# small.net
KiCad netlist of a schematic drawn in EAGLE
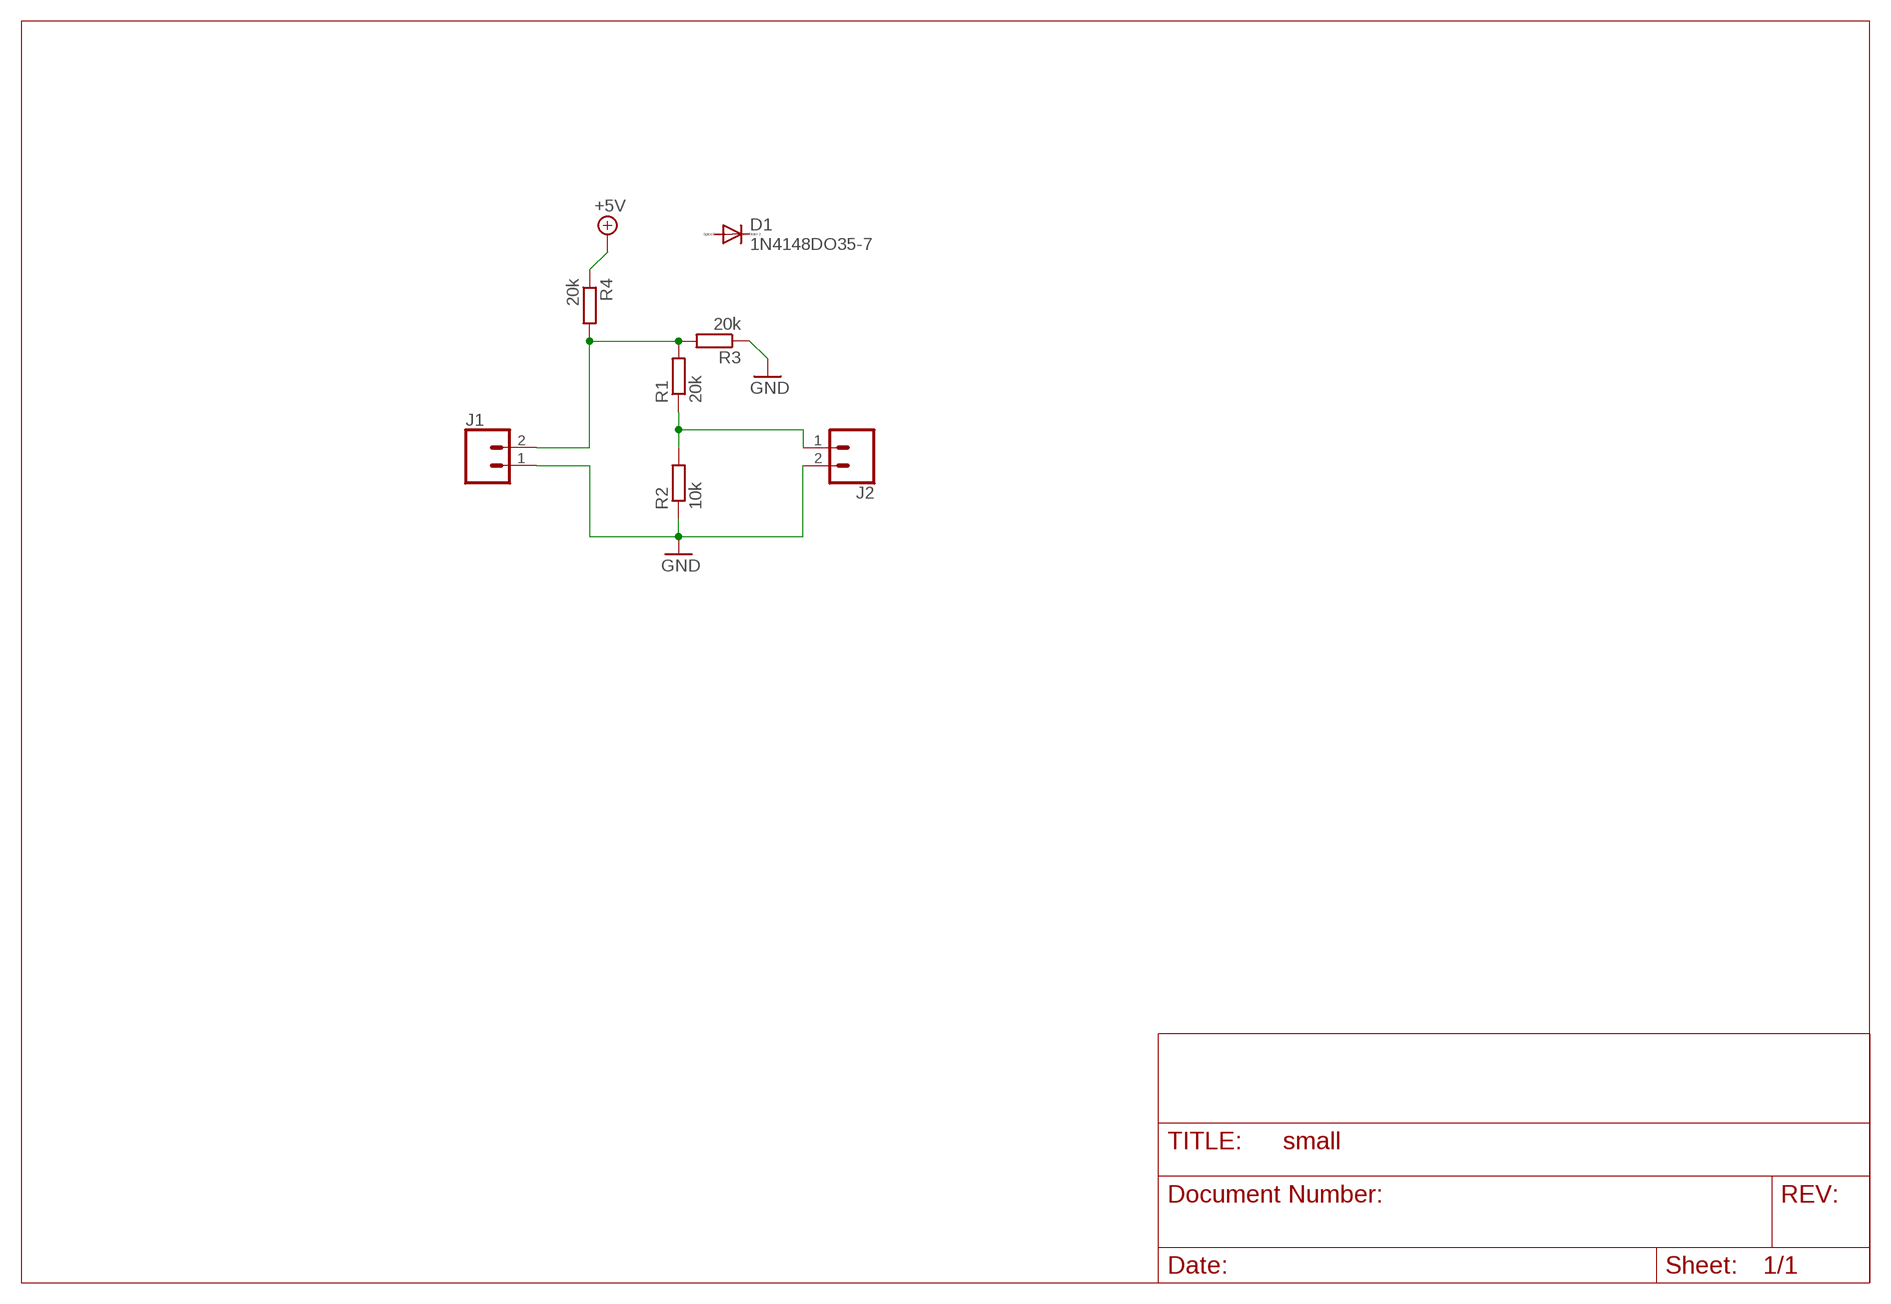
[diagram p0: schematic, sheet 1]

(export (version "E")
  (design (tool "Eeschema 10.0.6"))
  (components
    (comp (ref "D1")
      (value "1N4148DO35-7")
      (footprint "eagle-import:DO35-7")
      (libsource (lib "eagle-import") (part "1N4148DO35-7"))
    )
    (comp (ref "J1")
      (value "CONN_02")
      (footprint "eagle-import:1X02")
      (libsource (lib "eagle-import") (part "CONN_02"))
    )
    (comp (ref "J2")
      (value "CONN_02")
      (footprint "eagle-import:1X02")
      (libsource (lib "eagle-import") (part "CONN_02"))
    )
    (comp (ref "R1")
      (value "20k")
      (footprint "eagle-import:0204_5")
      (libsource (lib "eagle-import") (part "R-EU_0204/5"))
    )
    (comp (ref "R2")
      (value "10k")
      (footprint "eagle-import:0204_5")
      (libsource (lib "eagle-import") (part "R-EU_0204/5"))
    )
    (comp (ref "R3")
      (value "20k")
      (footprint "eagle-import:0204_5")
      (libsource (lib "eagle-import") (part "R-EU_0204/5"))
    )
    (comp (ref "R4")
      (value "20k")
      (footprint "eagle-import:0204_5")
      (libsource (lib "eagle-import") (part "R-EU_0204/5"))
    )
  )
  (nets
    (net (code "1") (name "+5V") (class "Default")
      (node (ref "R4") (pin "1") (pinfunction "1_1") (pintype "passive"))
    )
    (net (code "2") (name "GND") (class "Default")
      (node (ref "J1") (pin "1") (pinfunction "1_1") (pintype "passive"))
      (node (ref "J2") (pin "2") (pinfunction "2_2") (pintype "passive"))
      (node (ref "R2") (pin "1") (pinfunction "1_1") (pintype "passive"))
      (node (ref "R3") (pin "1") (pinfunction "1_1") (pintype "passive"))
    )
    (net (code "3") (name "Net-(J1-Pad2)") (class "Default")
      (node (ref "J1") (pin "2") (pinfunction "2_2") (pintype "passive"))
      (node (ref "R1") (pin "2") (pinfunction "2_2") (pintype "passive"))
      (node (ref "R3") (pin "2") (pinfunction "2_2") (pintype "passive"))
      (node (ref "R4") (pin "2") (pinfunction "2_2") (pintype "passive"))
    )
    (net (code "4") (name "Net-(J2-Pad1)") (class "Default")
      (node (ref "J2") (pin "1") (pinfunction "1_1") (pintype "passive"))
      (node (ref "R1") (pin "1") (pinfunction "1_1") (pintype "passive"))
      (node (ref "R2") (pin "2") (pinfunction "2_2") (pintype "passive"))
    )
    (net (code "5") (name "unconnected-(D1-PadA)") (class "Default")
      (node (ref "D1") (pin "A") (pinfunction "A_A") (pintype "passive"))
    )
    (net (code "6") (name "unconnected-(D1-PadC)") (class "Default")
      (node (ref "D1") (pin "C") (pinfunction "C_C") (pintype "passive"))
    )
  )
)
